# Sheet1.net
KiCad netlist of a schematic drawn in Altium Designer
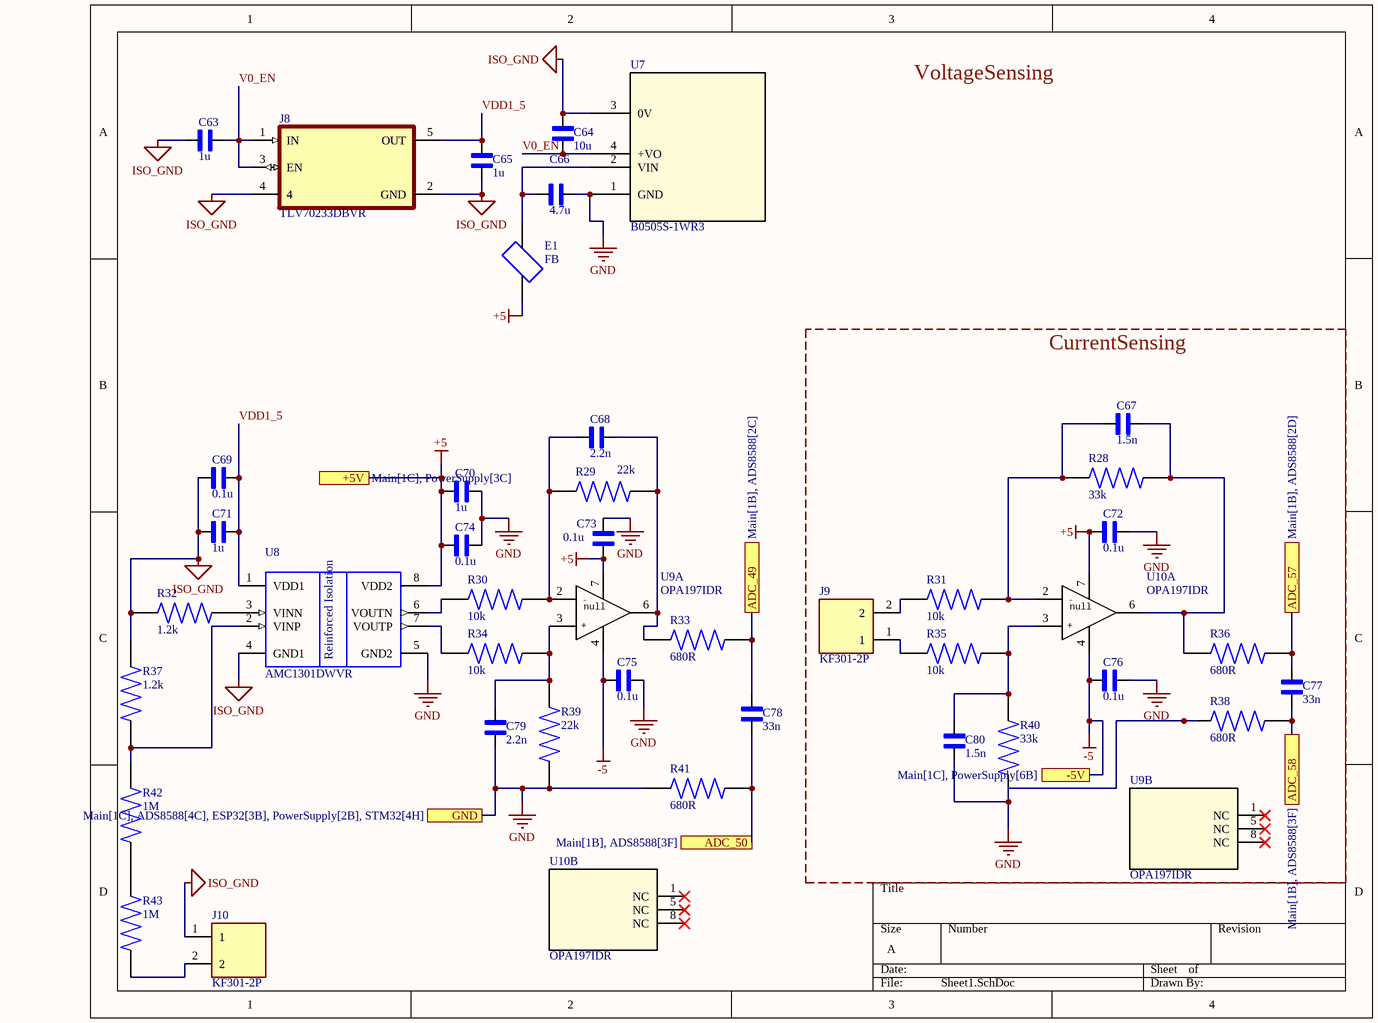
[diagram p0: Sheet1.SchDoc]

(export (version "E")
  (design (tool "Eeschema 10.0.6"))
  (components
    (comp (ref "C63")
      (value "1u")
      (footprint "0603Capacitor")
      (description "1uF,X7R,50V")
      (fields (field (name "MF") "AVX") (field (name "MP") "0603YC223KAT2A"))
      (libsource (lib "Schlib1") (part "0603_1u"))
    )
    (comp (ref "C64")
      (value "10u")
      (footprint "0603Capacitor")
      (description "10uF,X7R,50V")
      (fields (field (name "MF") "AVX") (field (name "MP") "0603YC223KAT2A"))
      (libsource (lib "Schlib1") (part "0603_10u"))
    )
    (comp (ref "C65")
      (value "1u")
      (footprint "0603Capacitor")
      (description "1uF,X7R,50V")
      (fields (field (name "MF") "AVX") (field (name "MP") "0603YC223KAT2A"))
      (libsource (lib "") (part "0603_1u_1"))
    )
    (comp (ref "C66")
      (value "4.7u")
      (footprint "0603Capacitor")
      (description "4.7uF,X7R,50V")
      (fields (field (name "MF") "AVX") (field (name "MP") "0603YC223KAT2A"))
      (libsource (lib "Schlib1") (part "0603_4.7u"))
    )
    (comp (ref "C67")
      (value "1.5n")
      (footprint "0603Capacitor")
      (description "1.5nf_C0G_50V")
      (fields (field (name "MF") "AVX") (field (name "MP") "0603YC223KAT2A"))
      (libsource (lib "Schlib1") (part "0603_1.5nf"))
    )
    (comp (ref "C68")
      (value "2.2n")
      (footprint "0603Capacitor")
      (description "2.2nF,C0G,50V")
      (fields (field (name "MF") "AVX") (field (name "MP") "0603YC223KAT2A"))
      (libsource (lib "") (part "0603_2.2n_1"))
    )
    (comp (ref "C69")
      (value "0.1u")
      (footprint "0603Capacitor")
      (description "100nf,X7R,50V")
      (fields (field (name "MF") "AVX") (field (name "MP") "0603YC223KAT2A"))
      (libsource (lib "Schlib1") (part "0603_0.1u"))
    )
    (comp (ref "C70")
      (value "1u")
      (footprint "0603Capacitor")
      (description "1uF,X7R,50V")
      (fields (field (name "MF") "AVX") (field (name "MP") "0603YC223KAT2A"))
      (libsource (lib "Schlib1") (part "0603_1u"))
    )
    (comp (ref "C71")
      (value "1u")
      (footprint "0603Capacitor")
      (description "1uF,X7R,50V")
      (fields (field (name "MF") "AVX") (field (name "MP") "0603YC223KAT2A"))
      (libsource (lib "Schlib1") (part "0603_1u"))
    )
    (comp (ref "C72")
      (value "0.1u")
      (footprint "0603Capacitor")
      (description "100nf,X7R,50V")
      (fields (field (name "MF") "AVX") (field (name "MP") "0603YC223KAT2A"))
      (libsource (lib "Schlib1") (part "0603_0.1u"))
    )
    (comp (ref "C73")
      (value "0.1u")
      (footprint "0603Capacitor")
      (description "100nf,X7R,50V")
      (fields (field (name "MF") "AVX") (field (name "MP") "0603YC223KAT2A"))
      (libsource (lib "") (part "0603_0.1u_1"))
    )
    (comp (ref "C74")
      (value "0.1u")
      (footprint "0603Capacitor")
      (description "100nf,X7R,50V")
      (fields (field (name "MF") "AVX") (field (name "MP") "0603YC223KAT2A"))
      (libsource (lib "Schlib1") (part "0603_0.1u"))
    )
    (comp (ref "C75")
      (value "0.1u")
      (footprint "0603Capacitor")
      (description "100nf,X7R,50V")
      (fields (field (name "MF") "AVX") (field (name "MP") "0603YC223KAT2A"))
      (libsource (lib "Schlib1") (part "0603_0.1u"))
    )
    (comp (ref "C76")
      (value "0.1u")
      (footprint "0603Capacitor")
      (description "100nf,X7R,50V")
      (fields (field (name "MF") "AVX") (field (name "MP") "0603YC223KAT2A"))
      (libsource (lib "Schlib1") (part "0603_0.1u"))
    )
    (comp (ref "C77")
      (value "33n")
      (footprint "CAPC1206")
      (description "33nf_C0G_50V")
      (fields (field (name "MF") "AVX") (field (name "MP") "0603YC223KAT2A"))
      (libsource (lib "Schlib1") (part "0603_33n"))
    )
    (comp (ref "C78")
      (value "33n")
      (footprint "CAPC1206")
      (description "33nf_C0G_50V")
      (fields (field (name "MF") "AVX") (field (name "MP") "0603YC223KAT2A"))
      (libsource (lib "Schlib1") (part "0603_33n"))
    )
    (comp (ref "C79")
      (value "2.2n")
      (footprint "0603Capacitor")
      (description "2.2nF,C0G,50V")
      (fields (field (name "MF") "AVX") (field (name "MP") "0603YC223KAT2A"))
      (libsource (lib "Schlib1") (part "0603_2.2n"))
    )
    (comp (ref "C80")
      (value "1.5n")
      (footprint "0603Capacitor")
      (description "1.5nf_C0G_50V")
      (fields (field (name "MF") "AVX") (field (name "MP") "0603YC223KAT2A"))
      (libsource (lib "") (part "0603_1.5nf_1"))
    )
    (comp (ref "E1")
      (value "FB")
      (footprint "FB_MI1206K601R-10")
      (description "600 Ohms @ 100 MHz 1 Power, Signal Line Ferrite Bead 1206 (3216 Metric) 1.5A 80mOhm")
      (fields (field (name "MF") "Laird-Signal Integrity") (field (name "MP") "MI1206K601R-10"))
      (libsource (lib "Schlib1") (part "MI1206K601R-10"))
    )
    (comp (ref "J8")
      (value "TLV70233DBVR")
      (footprint "TLV70233")
      (description "300-mA, high-PSRR, low-IQ, low-dropout voltage regulator with enable")
      (fields (field (name "MF") "Texas Instruments"))
      (libsource (lib "Schlib1") (part "TLV70233DBVR"))
    )
    (comp (ref "J9")
      (value "KF301-2P")
      (footprint "HANDSON_KF301-2P")
      (description "2 Pin Terminal Block 5mm Pitch")
      (fields (field (name "MF") "Handson Technology"))
      (libsource (lib "") (part "KF301-2P_1"))
    )
    (comp (ref "J10")
      (value "KF301-2P")
      (footprint "HANDSON_KF301-2P")
      (description "2 Pin Terminal Block 5mm Pitch")
      (fields (field (name "MF") "Handson Technology"))
      (libsource (lib "Schlib1") (part "KF301-2P"))
    )
    (comp (ref "R28")
      (value "33k")
      (footprint "0603Resistor")
      (description "33kOhm")
      (fields (field (name "MF") "Bourns") (field (name "MP") "CRT0603-FY-1000ELF"))
      (libsource (lib "Schlib1") (part "0603_33k_1"))
    )
    (comp (ref "R29")
      (value "22k")
      (footprint "0603Resistor")
      (description "22kOhm_0.1% to 0.5%")
      (fields (field (name "MF") "Bourns") (field (name "MP") "CRT0603-FY-1000ELF"))
      (libsource (lib "Schlib1") (part "0603_22k"))
    )
    (comp (ref "R30")
      (value "10k")
      (footprint "0603Resistor")
      (description "10kOhm")
      (fields (field (name "MF") "Bourns") (field (name "MP") "CRT0603-FY-1000ELF"))
      (libsource (lib "Schlib1") (part "0603_10k"))
    )
    (comp (ref "R31")
      (value "10k")
      (footprint "0603Resistor")
      (description "10kOhm")
      (fields (field (name "MF") "Bourns") (field (name "MP") "CRT0603-FY-1000ELF"))
      (libsource (lib "Schlib1") (part "0603_10k"))
    )
    (comp (ref "R32")
      (value "1.2k")
      (footprint "0603Resistor")
      (description "1.2k (0.1%-0.5%)")
      (fields (field (name "MF") "Bourns") (field (name "MP") "CRT0603-FY-1000ELF"))
      (libsource (lib "Schlib1") (part "0603_1.2K"))
    )
    (comp (ref "R33")
      (value "680R")
      (footprint "0603Resistor")
      (description "680Ohm-0.1%")
      (fields (field (name "MF") "Bourns") (field (name "MP") "CRT0603-FY-1000ELF"))
      (libsource (lib "Schlib1") (part "0603_680Ohm"))
    )
    (comp (ref "R34")
      (value "10k")
      (footprint "0603Resistor")
      (description "10kOhm")
      (fields (field (name "MF") "Bourns") (field (name "MP") "CRT0603-FY-1000ELF"))
      (libsource (lib "Schlib1") (part "0603_10k"))
    )
    (comp (ref "R35")
      (value "10k")
      (footprint "0603Resistor")
      (description "10kOhm")
      (fields (field (name "MF") "Bourns") (field (name "MP") "CRT0603-FY-1000ELF"))
      (libsource (lib "Schlib1") (part "0603_10k"))
    )
    (comp (ref "R36")
      (value "680R")
      (footprint "0603Resistor")
      (description "680Ohm-0.1%")
      (fields (field (name "MF") "Bourns") (field (name "MP") "CRT0603-FY-1000ELF"))
      (libsource (lib "Schlib1") (part "0603_680Ohm"))
    )
    (comp (ref "R37")
      (value "1.2k")
      (footprint "0603Resistor")
      (description "1.2k (0.1%-0.5%)")
      (fields (field (name "MF") "Bourns") (field (name "MP") "CRT0603-FY-1000ELF"))
      (libsource (lib "Schlib1") (part "0603_1.2K"))
    )
    (comp (ref "R38")
      (value "680R")
      (footprint "0603Resistor")
      (description "680Ohm-0.1%")
      (fields (field (name "MF") "Bourns") (field (name "MP") "CRT0603-FY-1000ELF"))
      (libsource (lib "Schlib1") (part "0603_680Ohm"))
    )
    (comp (ref "R39")
      (value "22k")
      (footprint "0603Resistor")
      (description "22kOhm_0.1% to 0.5%")
      (fields (field (name "MF") "Bourns") (field (name "MP") "CRT0603-FY-1000ELF"))
      (libsource (lib "Schlib1") (part "0603_22k"))
    )
    (comp (ref "R40")
      (value "33k")
      (footprint "0603Resistor")
      (description "33kOhm")
      (fields (field (name "MF") "Bourns") (field (name "MP") "CRT0603-FY-1000ELF"))
      (libsource (lib "Schlib1") (part "0603_33k_1"))
    )
    (comp (ref "R41")
      (value "680R")
      (footprint "0603Resistor")
      (description "680Ohm-0.1%")
      (fields (field (name "MF") "Bourns") (field (name "MP") "CRT0603-FY-1000ELF"))
      (libsource (lib "Schlib1") (part "0603_680Ohm"))
    )
    (comp (ref "R42")
      (value "1M")
      (footprint "1M_1206")
      (description "1M Ohms Â±1% 0.25W, 1/4W Chip Resistor 1206 (3216 Metric) Moisture Resistant Thick Film")
      (fields (field (name "MF") "Yageo") (field (name "MP") "RC1206JR-0713RL"))
      (libsource (lib "Schlib1") (part "1206-1M"))
    )
    (comp (ref "R43")
      (value "1M")
      (footprint "1M_1206")
      (description "1M Ohms Â±1% 0.25W, 1/4W Chip Resistor 1206 (3216 Metric) Moisture Resistant Thick Film")
      (fields (field (name "MF") "Yageo") (field (name "MP") "RC1206JR-0713RL"))
      (libsource (lib "Schlib1") (part "1206-1M"))
    )
    (comp (ref "U7")
      (value "B0505S-1WR3")
      (footprint "B0505S")
      (description "Description")
      (fields (field (name "COPYRIGHT") "Copyright (C) 2026 Ultra Librarian. All rights reserved."))
      (libsource (lib "Schlib1") (part "B0505S-1WR3"))
    )
    (comp (ref "U8")
      (value "AMC1301DWVR")
      (footprint "AMC1301")
      (description "250 mV-Input Precision Reinforced Isolated Amplifier for Current Sensing 8-SOIC -40 to 125")
      (fields (field (name "MF") "Texas Instruments"))
      (libsource (lib "Schlib1") (part "AMC1301DWVR"))
    )
    (comp (ref "U9")
      (value "OPA197IDR")
      (footprint "D0008A-MFG")
      (description "Single, 36-V, precision, rail-to-rail input output, low offset voltage op amp 8-SOIC -40 to 125")
      (fields (field (name "COPYRIGHT") "Copyright (C) 2026 Ultra Librarian. All rights reserved."))
      (libsource (lib "Schlib1") (part "OPA197IDR"))
    )
    (comp (ref "U10")
      (value "OPA197IDR")
      (footprint "D0008A-MFG")
      (description "Single, 36-V, precision, rail-to-rail input output, low offset voltage op amp 8-SOIC -40 to 125")
      (fields (field (name "COPYRIGHT") "Copyright (C) 2026 Ultra Librarian. All rights reserved."))
      (libsource (lib "Schlib1") (part "OPA197IDR"))
    )
  )
  (nets
    (net (code "1") (name "+5") (class "Default")
      (node (ref "C70") (pin "1") (pinfunction "1_1") (pintype "passive"))
      (node (ref "C72") (pin "1") (pinfunction "1_1") (pintype "passive"))
      (node (ref "C73") (pin "1") (pinfunction "1_1") (pintype "passive"))
      (node (ref "C74") (pin "1") (pinfunction "1_1") (pintype "passive"))
      (node (ref "E1") (pin "1") (pinfunction "1_1") (pintype "passive"))
      (node (ref "U10") (pin "7") (pinfunction "V+_7") (pintype "power_in"))
      (node (ref "U8") (pin "8") (pinfunction "VDD2_8") (pintype "power_in"))
      (node (ref "U9") (pin "7") (pinfunction "V+_7") (pintype "power_in"))
    )
    (net (code "2") (name "-5") (class "Default")
      (node (ref "C75") (pin "1") (pinfunction "1_1") (pintype "passive"))
      (node (ref "C76") (pin "1") (pinfunction "1_1") (pintype "passive"))
      (node (ref "U10") (pin "4") (pinfunction "V-_4") (pintype "power_in"))
      (node (ref "U9") (pin "4") (pinfunction "V-_4") (pintype "power_in"))
    )
    (net (code "3") (name "/ADC_49") (class "Default")
      (node (ref "C78") (pin "2") (pinfunction "2_2") (pintype "passive"))
      (node (ref "R33") (pin "2") (pinfunction "2_2") (pintype "passive"))
    )
    (net (code "4") (name "/ADC_50") (class "Default")
      (node (ref "C78") (pin "1") (pinfunction "1_1") (pintype "passive"))
      (node (ref "R41") (pin "2") (pinfunction "2_2") (pintype "passive"))
    )
    (net (code "5") (name "/ADC_57") (class "Default")
      (node (ref "C77") (pin "2") (pinfunction "2_2") (pintype "passive"))
      (node (ref "R36") (pin "2") (pinfunction "2_2") (pintype "passive"))
    )
    (net (code "6") (name "/ADC_58") (class "Default")
      (node (ref "C77") (pin "1") (pinfunction "1_1") (pintype "passive"))
      (node (ref "R38") (pin "2") (pinfunction "2_2") (pintype "passive"))
    )
    (net (code "7") (name "/V0_EN") (class "Default")
      (node (ref "C63") (pin "2") (pinfunction "2_2") (pintype "passive"))
      (node (ref "C64") (pin "1") (pinfunction "1_1") (pintype "passive"))
      (node (ref "J8") (pin "1") (pinfunction "IN_1") (pintype "input"))
      (node (ref "J8") (pin "3") (pinfunction "EN_3") (pintype "bidirectional"))
      (node (ref "U7") (pin "4") (pinfunction "+VO_4") (pintype "power_in"))
    )
    (net (code "8") (name "/VDD1_5") (class "Default")
      (node (ref "C65") (pin "2") (pinfunction "2_2") (pintype "passive"))
      (node (ref "C69") (pin "2") (pinfunction "2_2") (pintype "passive"))
      (node (ref "C71") (pin "2") (pinfunction "2_2") (pintype "passive"))
      (node (ref "J8") (pin "5") (pinfunction "OUT_5") (pintype "power_in"))
      (node (ref "U8") (pin "1") (pinfunction "VDD1_1") (pintype "power_in"))
    )
    (net (code "9") (name "GND") (class "Default")
      (node (ref "C66") (pin "2") (pinfunction "2_2") (pintype "passive"))
      (node (ref "C70") (pin "2") (pinfunction "2_2") (pintype "passive"))
      (node (ref "C72") (pin "2") (pinfunction "2_2") (pintype "passive"))
      (node (ref "C73") (pin "2") (pinfunction "2_2") (pintype "passive"))
      (node (ref "C74") (pin "2") (pinfunction "2_2") (pintype "passive"))
      (node (ref "C75") (pin "2") (pinfunction "2_2") (pintype "passive"))
      (node (ref "C76") (pin "2") (pinfunction "2_2") (pintype "passive"))
      (node (ref "C79") (pin "1") (pinfunction "1_1") (pintype "passive"))
      (node (ref "C80") (pin "1") (pinfunction "1_1") (pintype "passive"))
      (node (ref "R38") (pin "1") (pinfunction "1_1") (pintype "passive"))
      (node (ref "R39") (pin "1") (pinfunction "1_1") (pintype "passive"))
      (node (ref "R40") (pin "1") (pinfunction "1_1") (pintype "passive"))
      (node (ref "R41") (pin "1") (pinfunction "1_1") (pintype "passive"))
      (node (ref "U7") (pin "1") (pinfunction "GND_1") (pintype "power_in"))
      (node (ref "U8") (pin "5") (pinfunction "GND2_5") (pintype "power_in"))
    )
    (net (code "10") (name "ISO_GND") (class "Default")
      (node (ref "C63") (pin "1") (pinfunction "1_1") (pintype "passive"))
      (node (ref "C64") (pin "2") (pinfunction "2_2") (pintype "passive"))
      (node (ref "C65") (pin "1") (pinfunction "1_1") (pintype "passive"))
      (node (ref "C69") (pin "1") (pinfunction "1_1") (pintype "passive"))
      (node (ref "C71") (pin "1") (pinfunction "1_1") (pintype "passive"))
      (node (ref "J10") (pin "1") (pinfunction "1_1") (pintype "passive"))
      (node (ref "J8") (pin "2") (pinfunction "GND_2") (pintype "power_in"))
      (node (ref "J8") (pin "4") (pinfunction "4_4") (pintype "power_in"))
      (node (ref "R32") (pin "1") (pinfunction "1_1") (pintype "passive"))
      (node (ref "R37") (pin "2") (pinfunction "2_2") (pintype "passive"))
      (node (ref "U7") (pin "3") (pinfunction "0V_3") (pintype "passive"))
      (node (ref "U8") (pin "4") (pinfunction "GND1_4") (pintype "power_in"))
    )
    (net (code "11") (name "Net-(J9-Pad1)") (class "Default")
      (node (ref "J9") (pin "1") (pinfunction "1_1") (pintype "passive"))
      (node (ref "R35") (pin "1") (pinfunction "1_1") (pintype "passive"))
    )
    (net (code "12") (name "Net-(J9-Pad2)") (class "Default")
      (node (ref "J9") (pin "2") (pinfunction "2_2") (pintype "passive"))
      (node (ref "R31") (pin "1") (pinfunction "1_1") (pintype "passive"))
    )
    (net (code "13") (name "Net-(J10-Pad2)") (class "Default")
      (node (ref "J10") (pin "2") (pinfunction "2_2") (pintype "passive"))
      (node (ref "R43") (pin "1") (pinfunction "1_1") (pintype "passive"))
    )
    (net (code "14") (name "Net-(R42-Pad1)") (class "Default")
      (node (ref "R42") (pin "1") (pinfunction "1_1") (pintype "passive"))
      (node (ref "R43") (pin "2") (pinfunction "2_2") (pintype "passive"))
    )
    (net (code "15") (name "Net-(U7-VIN)") (class "Default")
      (node (ref "C66") (pin "1") (pinfunction "1_1") (pintype "passive"))
      (node (ref "E1") (pin "2") (pinfunction "2_2") (pintype "passive"))
      (node (ref "U7") (pin "2") (pinfunction "VIN_2") (pintype "power_in"))
    )
    (net (code "16") (name "Net-(U8-VINN)") (class "Default")
      (node (ref "R32") (pin "2") (pinfunction "2_2") (pintype "passive"))
      (node (ref "U8") (pin "3") (pinfunction "VINN_3") (pintype "input"))
    )
    (net (code "17") (name "Net-(U8-VINP)") (class "Default")
      (node (ref "R37") (pin "1") (pinfunction "1_1") (pintype "passive"))
      (node (ref "R42") (pin "2") (pinfunction "2_2") (pintype "passive"))
      (node (ref "U8") (pin "2") (pinfunction "VINP_2") (pintype "input"))
    )
    (net (code "18") (name "Net-(U8-VOUTN)") (class "Default")
      (node (ref "R30") (pin "1") (pinfunction "1_1") (pintype "passive"))
      (node (ref "U8") (pin "6") (pinfunction "VOUTN_6") (pintype "output"))
    )
    (net (code "19") (name "Net-(U8-VOUTP)") (class "Default")
      (node (ref "R34") (pin "1") (pinfunction "1_1") (pintype "passive"))
      (node (ref "U8") (pin "7") (pinfunction "VOUTP_7") (pintype "output"))
    )
    (net (code "20") (name "Net-(U9A-+IN)") (class "Default")
      (node (ref "C79") (pin "2") (pinfunction "2_2") (pintype "passive"))
      (node (ref "R34") (pin "2") (pinfunction "2_2") (pintype "passive"))
      (node (ref "R39") (pin "2") (pinfunction "2_2") (pintype "passive"))
      (node (ref "U9") (pin "3") (pinfunction "+IN_3") (pintype "tri_state"))
    )
    (net (code "21") (name "Net-(U9A--IN)") (class "Default")
      (node (ref "C68") (pin "1") (pinfunction "1_1") (pintype "passive"))
      (node (ref "R29") (pin "1") (pinfunction "1_1") (pintype "passive"))
      (node (ref "R30") (pin "2") (pinfunction "2_2") (pintype "passive"))
      (node (ref "U9") (pin "2") (pinfunction "-IN_2") (pintype "tri_state"))
    )
    (net (code "22") (name "Net-(U9A-OUT)") (class "Default")
      (node (ref "C68") (pin "2") (pinfunction "2_2") (pintype "passive"))
      (node (ref "R29") (pin "2") (pinfunction "2_2") (pintype "passive"))
      (node (ref "R33") (pin "1") (pinfunction "1_1") (pintype "passive"))
      (node (ref "U9") (pin "6") (pinfunction "OUT_6") (pintype "passive"))
    )
    (net (code "23") (name "Net-(U10A-+IN)") (class "Default")
      (node (ref "C80") (pin "2") (pinfunction "2_2") (pintype "passive"))
      (node (ref "R35") (pin "2") (pinfunction "2_2") (pintype "passive"))
      (node (ref "R40") (pin "2") (pinfunction "2_2") (pintype "passive"))
      (node (ref "U10") (pin "3") (pinfunction "+IN_3") (pintype "tri_state"))
    )
    (net (code "24") (name "Net-(U10A--IN)") (class "Default")
      (node (ref "C67") (pin "1") (pinfunction "1_1") (pintype "passive"))
      (node (ref "R28") (pin "1") (pinfunction "1_1") (pintype "passive"))
      (node (ref "R31") (pin "2") (pinfunction "2_2") (pintype "passive"))
      (node (ref "U10") (pin "2") (pinfunction "-IN_2") (pintype "tri_state"))
    )
    (net (code "25") (name "Net-(U10A-OUT)") (class "Default")
      (node (ref "C67") (pin "2") (pinfunction "2_2") (pintype "passive"))
      (node (ref "R28") (pin "2") (pinfunction "2_2") (pintype "passive"))
      (node (ref "R36") (pin "1") (pinfunction "1_1") (pintype "passive"))
      (node (ref "U10") (pin "6") (pinfunction "OUT_6") (pintype "passive"))
    )
    (net (code "26") (name "unconnected-(U9B-NC-Pad1)") (class "Default")
      (node (ref "U9") (pin "1") (pinfunction "NC_1") (pintype "passive+no_connect"))
    )
    (net (code "27") (name "unconnected-(U9B-NC-Pad5)") (class "Default")
      (node (ref "U9") (pin "5") (pinfunction "NC_5") (pintype "passive+no_connect"))
    )
    (net (code "28") (name "unconnected-(U9B-NC-Pad8)") (class "Default")
      (node (ref "U9") (pin "8") (pinfunction "NC_8") (pintype "passive+no_connect"))
    )
    (net (code "29") (name "unconnected-(U10B-NC-Pad1)") (class "Default")
      (node (ref "U10") (pin "1") (pinfunction "NC_1") (pintype "passive+no_connect"))
    )
    (net (code "30") (name "unconnected-(U10B-NC-Pad5)") (class "Default")
      (node (ref "U10") (pin "5") (pinfunction "NC_5") (pintype "passive+no_connect"))
    )
    (net (code "31") (name "unconnected-(U10B-NC-Pad8)") (class "Default")
      (node (ref "U10") (pin "8") (pinfunction "NC_8") (pintype "passive+no_connect"))
    )
  )
)
